# MainCircuit.net
KiCad netlist of a schematic drawn in EAGLE
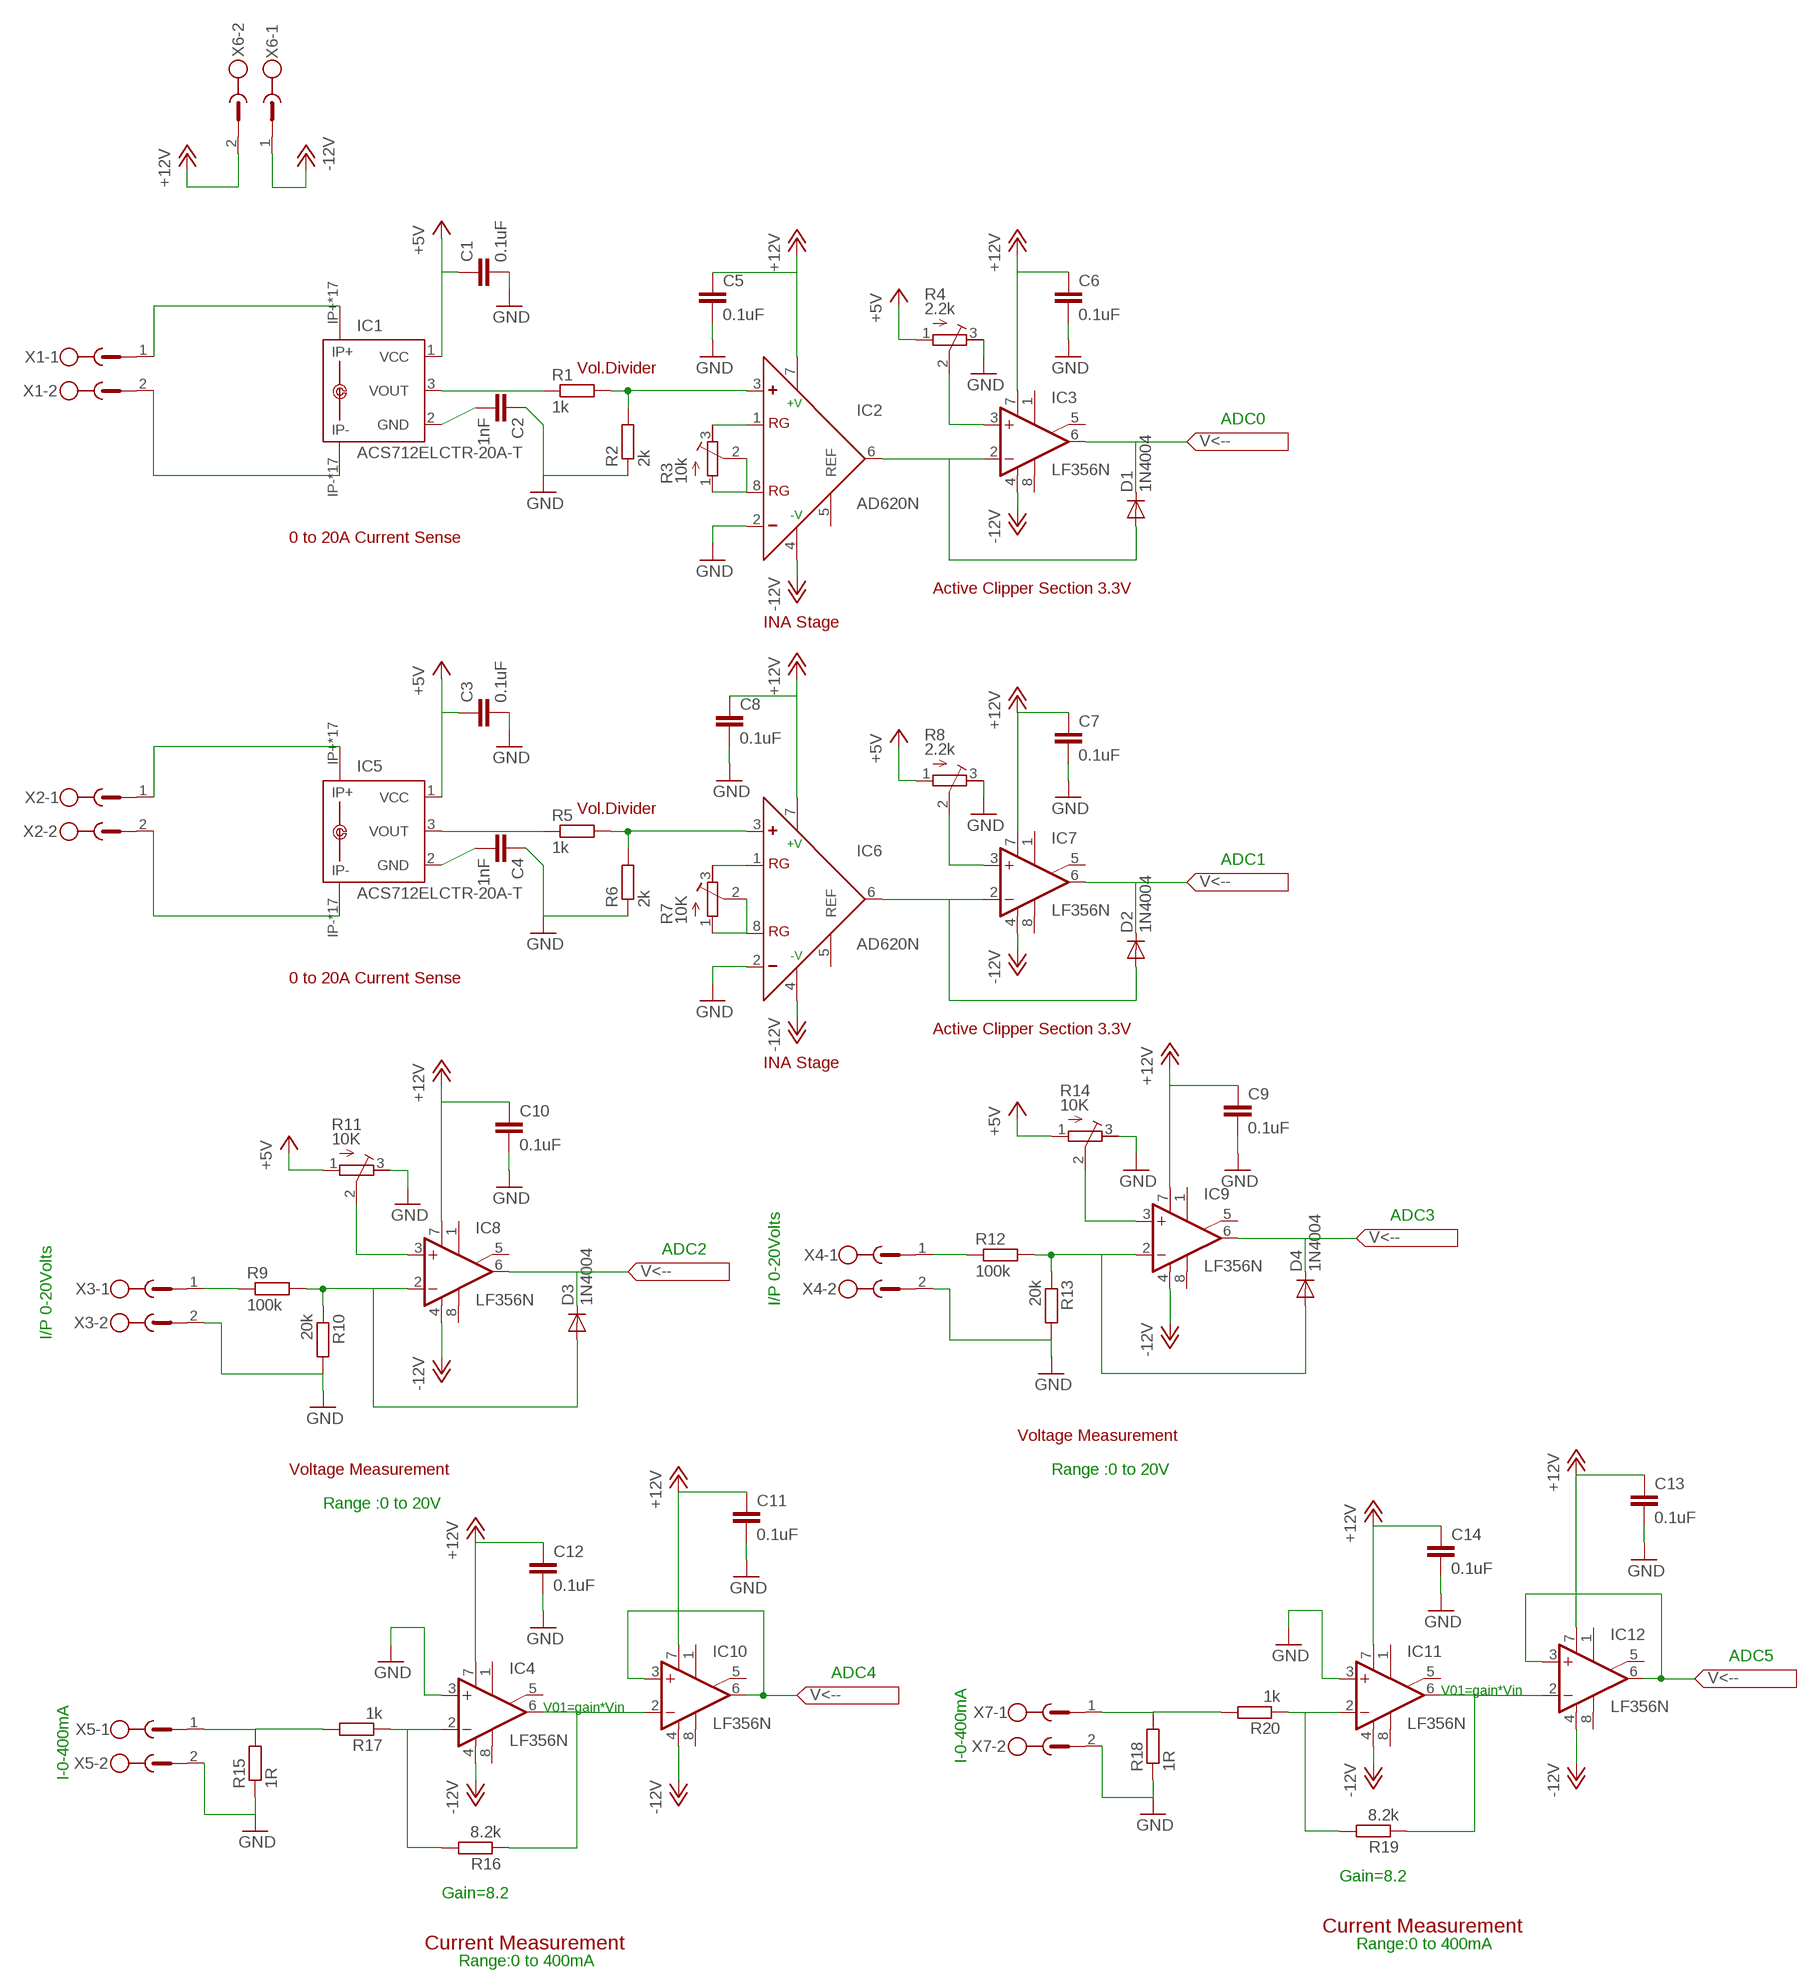
[diagram p0: schematic, sheet 1]

(export (version "E")
  (design (tool "Eeschema 10.0.6"))
  (components
    (comp (ref "C1")
      (value "0.1uF")
      (footprint "eagle-import:C025-024X044")
      (libsource (lib "eagle-import") (part "C-EU025-024X044"))
    )
    (comp (ref "C2")
      (value "1nF")
      (footprint "eagle-import:C025-024X044")
      (libsource (lib "eagle-import") (part "C-EU025-024X044"))
    )
    (comp (ref "C3")
      (value "0.1uF")
      (footprint "eagle-import:C025-024X044")
      (libsource (lib "eagle-import") (part "C-EU025-024X044"))
    )
    (comp (ref "C4")
      (value "1nF")
      (footprint "eagle-import:C025-024X044")
      (libsource (lib "eagle-import") (part "C-EU025-024X044"))
    )
    (comp (ref "C5")
      (value "0.1uF")
      (footprint "eagle-import:C025-024X044")
      (libsource (lib "eagle-import") (part "C-EU025-024X044"))
    )
    (comp (ref "C6")
      (value "0.1uF")
      (footprint "eagle-import:C025-024X044")
      (libsource (lib "eagle-import") (part "C-EU025-024X044"))
    )
    (comp (ref "C7")
      (value "0.1uF")
      (footprint "eagle-import:C025-024X044")
      (libsource (lib "eagle-import") (part "C-EU025-024X044"))
    )
    (comp (ref "C8")
      (value "0.1uF")
      (footprint "eagle-import:C025-024X044")
      (libsource (lib "eagle-import") (part "C-EU025-024X044"))
    )
    (comp (ref "C9")
      (value "0.1uF")
      (footprint "eagle-import:C025-024X044")
      (libsource (lib "eagle-import") (part "C-EU025-024X044"))
    )
    (comp (ref "C10")
      (value "0.1uF")
      (footprint "eagle-import:C025-024X044")
      (libsource (lib "eagle-import") (part "C-EU025-024X044"))
    )
    (comp (ref "C11")
      (value "0.1uF")
      (footprint "eagle-import:C025-024X044")
      (libsource (lib "eagle-import") (part "C-EU025-024X044"))
    )
    (comp (ref "C12")
      (value "0.1uF")
      (footprint "eagle-import:C025-024X044")
      (libsource (lib "eagle-import") (part "C-EU025-024X044"))
    )
    (comp (ref "C13")
      (value "0.1uF")
      (footprint "eagle-import:C025-024X044")
      (libsource (lib "eagle-import") (part "C-EU025-024X044"))
    )
    (comp (ref "C14")
      (value "0.1uF")
      (footprint "eagle-import:C025-024X044")
      (libsource (lib "eagle-import") (part "C-EU025-024X044"))
    )
    (comp (ref "D1")
      (value "1N4004")
      (footprint "eagle-import:DO41-10")
      (libsource (lib "eagle-import") (part "1N4004"))
    )
    (comp (ref "D2")
      (value "1N4004")
      (footprint "eagle-import:DO41-10")
      (libsource (lib "eagle-import") (part "1N4004"))
    )
    (comp (ref "D3")
      (value "1N4004")
      (footprint "eagle-import:DO41-10")
      (libsource (lib "eagle-import") (part "1N4004"))
    )
    (comp (ref "D4")
      (value "1N4004")
      (footprint "eagle-import:DO41-10")
      (libsource (lib "eagle-import") (part "1N4004"))
    )
    (comp (ref "IC1")
      (value "ACS712ELCTR-20A-T")
      (footprint "eagle-import:CB-PFF")
      (fields (field (name "MPN") "ACS758ECB-200B-PFF-T"))
      (libsource (lib "eagle-import") (part "ACS758ECB-200B-PFF-T"))
    )
    (comp (ref "IC2")
      (value "AD620N")
      (footprint "eagle-import:DIL08")
      (fields (field (name "MF") "ALTERA CORPORATION") (field (name "MPN") "AD620AN"))
      (libsource (lib "eagle-import") (part "AD620N"))
    )
    (comp (ref "IC3")
      (value "LF356N")
      (footprint "eagle-import:DIL08")
      (libsource (lib "eagle-import") (part "LF356N"))
    )
    (comp (ref "IC4")
      (value "LF356N")
      (footprint "eagle-import:DIL08")
      (libsource (lib "eagle-import") (part "LF356N"))
    )
    (comp (ref "IC5")
      (value "ACS712ELCTR-20A-T")
      (footprint "eagle-import:CB-PFF")
      (fields (field (name "MPN") "ACS758ECB-200B-PFF-T"))
      (libsource (lib "eagle-import") (part "ACS758ECB-200B-PFF-T"))
    )
    (comp (ref "IC6")
      (value "AD620N")
      (footprint "eagle-import:DIL08")
      (fields (field (name "MF") "ALTERA CORPORATION") (field (name "MPN") "AD620AN"))
      (libsource (lib "eagle-import") (part "AD620N"))
    )
    (comp (ref "IC7")
      (value "LF356N")
      (footprint "eagle-import:DIL08")
      (libsource (lib "eagle-import") (part "LF356N"))
    )
    (comp (ref "IC8")
      (value "LF356N")
      (footprint "eagle-import:DIL08")
      (libsource (lib "eagle-import") (part "LF356N"))
    )
    (comp (ref "IC9")
      (value "LF356N")
      (footprint "eagle-import:DIL08")
      (libsource (lib "eagle-import") (part "LF356N"))
    )
    (comp (ref "IC10")
      (value "LF356N")
      (footprint "eagle-import:DIL08")
      (libsource (lib "eagle-import") (part "LF356N"))
    )
    (comp (ref "IC11")
      (value "LF356N")
      (footprint "eagle-import:DIL08")
      (libsource (lib "eagle-import") (part "LF356N"))
    )
    (comp (ref "IC12")
      (value "LF356N")
      (footprint "eagle-import:DIL08")
      (libsource (lib "eagle-import") (part "LF356N"))
    )
    (comp (ref "R1")
      (value "1k")
      (footprint "eagle-import:0204_7")
      (libsource (lib "eagle-import") (part "R-EU_0204/7"))
    )
    (comp (ref "R2")
      (value "2k")
      (footprint "eagle-import:0204_7")
      (libsource (lib "eagle-import") (part "R-EU_0204/7"))
    )
    (comp (ref "R3")
      (value "10k")
      (footprint "eagle-import:RTRIM64W")
      (libsource (lib "eagle-import") (part "R-TRIMM64W"))
    )
    (comp (ref "R4")
      (value "2.2k")
      (footprint "eagle-import:RTRIM64W")
      (libsource (lib "eagle-import") (part "R-TRIMM64W"))
    )
    (comp (ref "R5")
      (value "1k")
      (footprint "eagle-import:0204_7")
      (libsource (lib "eagle-import") (part "R-EU_0204/7"))
    )
    (comp (ref "R6")
      (value "2k")
      (footprint "eagle-import:0204_7")
      (libsource (lib "eagle-import") (part "R-EU_0204/7"))
    )
    (comp (ref "R7")
      (value "10K")
      (footprint "eagle-import:RTRIM64W")
      (libsource (lib "eagle-import") (part "R-TRIMM64W"))
    )
    (comp (ref "R8")
      (value "2.2k")
      (footprint "eagle-import:RTRIM64W")
      (libsource (lib "eagle-import") (part "R-TRIMM64W"))
    )
    (comp (ref "R9")
      (value "100k")
      (footprint "eagle-import:0207_5V")
      (libsource (lib "eagle-import") (part "R-EU_0207/5V"))
    )
    (comp (ref "R10")
      (value "20k")
      (footprint "eagle-import:0207_5V")
      (libsource (lib "eagle-import") (part "R-EU_0207/5V"))
    )
    (comp (ref "R11")
      (value "10K")
      (footprint "eagle-import:RTRIM64W")
      (libsource (lib "eagle-import") (part "R-TRIMM64W"))
    )
    (comp (ref "R12")
      (value "100k")
      (footprint "eagle-import:0207_5V")
      (libsource (lib "eagle-import") (part "R-EU_0207/5V"))
    )
    (comp (ref "R13")
      (value "20k")
      (footprint "eagle-import:0207_5V")
      (libsource (lib "eagle-import") (part "R-EU_0207/5V"))
    )
    (comp (ref "R14")
      (value "10K")
      (footprint "eagle-import:RTRIM64W")
      (libsource (lib "eagle-import") (part "R-TRIMM64W"))
    )
    (comp (ref "R15")
      (value "1R")
      (footprint "eagle-import:0204_7")
      (libsource (lib "eagle-import") (part "R-EU_0204/7"))
    )
    (comp (ref "R16")
      (value "8.2k")
      (footprint "eagle-import:0204_7")
      (libsource (lib "eagle-import") (part "R-EU_0204/7"))
    )
    (comp (ref "R17")
      (value "1k")
      (footprint "eagle-import:0204_7")
      (libsource (lib "eagle-import") (part "R-EU_0204/7"))
    )
    (comp (ref "R18")
      (value "1R")
      (footprint "eagle-import:0204_7")
      (libsource (lib "eagle-import") (part "R-EU_0204/7"))
    )
    (comp (ref "R19")
      (value "8.2k")
      (footprint "eagle-import:0204_7")
      (libsource (lib "eagle-import") (part "R-EU_0204/7"))
    )
    (comp (ref "R20")
      (value "1k")
      (footprint "eagle-import:0204_7")
      (libsource (lib "eagle-import") (part "R-EU_0204/7"))
    )
    (comp (ref "X1")
      (value "MSTBV2")
      (footprint "eagle-import:MSTBV2")
      (libsource (lib "eagle-import") (part "MSTBV2"))
    )
    (comp (ref "X2")
      (value "MSTBV2")
      (footprint "eagle-import:MSTBV2")
      (libsource (lib "eagle-import") (part "MSTBV2"))
    )
    (comp (ref "X3")
      (value "MSTBV2")
      (footprint "eagle-import:MSTBV2")
      (libsource (lib "eagle-import") (part "MSTBV2"))
    )
    (comp (ref "X4")
      (value "MSTBV2")
      (footprint "eagle-import:MSTBV2")
      (libsource (lib "eagle-import") (part "MSTBV2"))
    )
    (comp (ref "X5")
      (value "MSTBV2")
      (footprint "eagle-import:MSTBV2")
      (libsource (lib "eagle-import") (part "MSTBV2"))
    )
    (comp (ref "X6")
      (value "MSTBV2")
      (footprint "eagle-import:MSTBV2")
      (libsource (lib "eagle-import") (part "MSTBV2"))
    )
    (comp (ref "X7")
      (value "MSTBV2")
      (footprint "eagle-import:MSTBV2")
      (libsource (lib "eagle-import") (part "MSTBV2"))
    )
  )
  (nets
    (net (code "1") (name "+5V") (class "Default")
      (node (ref "C1") (pin "1") (pinfunction "1_1") (pintype "passive"))
      (node (ref "C3") (pin "1") (pinfunction "1_1") (pintype "passive"))
      (node (ref "IC1") (pin "1") (pinfunction "VCC_1") (pintype "power_in"))
      (node (ref "IC5") (pin "1") (pinfunction "VCC_1") (pintype "power_in"))
      (node (ref "R11") (pin "1") (pinfunction "A_1") (pintype "passive"))
      (node (ref "R14") (pin "1") (pinfunction "A_1") (pintype "passive"))
      (node (ref "R4") (pin "1") (pinfunction "A_1") (pintype "passive"))
      (node (ref "R8") (pin "1") (pinfunction "A_1") (pintype "passive"))
    )
    (net (code "2") (name "+12V") (class "Default")
      (node (ref "C10") (pin "1") (pinfunction "1_1") (pintype "passive"))
      (node (ref "C11") (pin "1") (pinfunction "1_1") (pintype "passive"))
      (node (ref "C12") (pin "1") (pinfunction "1_1") (pintype "passive"))
      (node (ref "C13") (pin "1") (pinfunction "1_1") (pintype "passive"))
      (node (ref "C14") (pin "1") (pinfunction "1_1") (pintype "passive"))
      (node (ref "C5") (pin "1") (pinfunction "1_1") (pintype "passive"))
      (node (ref "C6") (pin "1") (pinfunction "1_1") (pintype "passive"))
      (node (ref "C7") (pin "1") (pinfunction "1_1") (pintype "passive"))
      (node (ref "C8") (pin "1") (pinfunction "1_1") (pintype "passive"))
      (node (ref "C9") (pin "1") (pinfunction "1_1") (pintype "passive"))
      (node (ref "IC10") (pin "7") (pinfunction "V+_7") (pintype "power_in"))
      (node (ref "IC11") (pin "7") (pinfunction "V+_7") (pintype "power_in"))
      (node (ref "IC12") (pin "7") (pinfunction "V+_7") (pintype "power_in"))
      (node (ref "IC2") (pin "7") (pinfunction "+V_7") (pintype "power_in"))
      (node (ref "IC3") (pin "7") (pinfunction "V+_7") (pintype "power_in"))
      (node (ref "IC4") (pin "7") (pinfunction "V+_7") (pintype "power_in"))
      (node (ref "IC6") (pin "7") (pinfunction "+V_7") (pintype "power_in"))
      (node (ref "IC7") (pin "7") (pinfunction "V+_7") (pintype "power_in"))
      (node (ref "IC8") (pin "7") (pinfunction "V+_7") (pintype "power_in"))
      (node (ref "IC9") (pin "7") (pinfunction "V+_7") (pintype "power_in"))
      (node (ref "X6") (pin "2") (pinfunction "SK_2") (pintype "passive"))
    )
    (net (code "3") (name "-12V") (class "Default")
      (node (ref "IC10") (pin "4") (pinfunction "V-_4") (pintype "power_in"))
      (node (ref "IC11") (pin "4") (pinfunction "V-_4") (pintype "power_in"))
      (node (ref "IC12") (pin "4") (pinfunction "V-_4") (pintype "power_in"))
      (node (ref "IC2") (pin "4") (pinfunction "-V_4") (pintype "power_in"))
      (node (ref "IC3") (pin "4") (pinfunction "V-_4") (pintype "power_in"))
      (node (ref "IC4") (pin "4") (pinfunction "V-_4") (pintype "power_in"))
      (node (ref "IC6") (pin "4") (pinfunction "-V_4") (pintype "power_in"))
      (node (ref "IC7") (pin "4") (pinfunction "V-_4") (pintype "power_in"))
      (node (ref "IC8") (pin "4") (pinfunction "V-_4") (pintype "power_in"))
      (node (ref "IC9") (pin "4") (pinfunction "V-_4") (pintype "power_in"))
      (node (ref "X6") (pin "1") (pinfunction "SK_1") (pintype "passive"))
    )
    (net (code "4") (name "GND") (class "Default")
      (node (ref "C1") (pin "2") (pinfunction "2_2") (pintype "passive"))
      (node (ref "C10") (pin "2") (pinfunction "2_2") (pintype "passive"))
      (node (ref "C11") (pin "2") (pinfunction "2_2") (pintype "passive"))
      (node (ref "C12") (pin "2") (pinfunction "2_2") (pintype "passive"))
      (node (ref "C13") (pin "2") (pinfunction "2_2") (pintype "passive"))
      (node (ref "C14") (pin "2") (pinfunction "2_2") (pintype "passive"))
      (node (ref "C2") (pin "1") (pinfunction "1_1") (pintype "passive"))
      (node (ref "C3") (pin "2") (pinfunction "2_2") (pintype "passive"))
      (node (ref "C4") (pin "1") (pinfunction "1_1") (pintype "passive"))
      (node (ref "C5") (pin "2") (pinfunction "2_2") (pintype "passive"))
      (node (ref "C6") (pin "2") (pinfunction "2_2") (pintype "passive"))
      (node (ref "C7") (pin "2") (pinfunction "2_2") (pintype "passive"))
      (node (ref "C8") (pin "2") (pinfunction "2_2") (pintype "passive"))
      (node (ref "C9") (pin "2") (pinfunction "2_2") (pintype "passive"))
      (node (ref "IC11") (pin "3") (pinfunction "+IN_3") (pintype "input"))
      (node (ref "IC2") (pin "2") (pinfunction "-_2") (pintype "input"))
      (node (ref "IC4") (pin "3") (pinfunction "+IN_3") (pintype "input"))
      (node (ref "IC6") (pin "2") (pinfunction "-_2") (pintype "input"))
      (node (ref "R10") (pin "2") (pinfunction "2_2") (pintype "passive"))
      (node (ref "R11") (pin "3") (pinfunction "E_3") (pintype "passive"))
      (node (ref "R13") (pin "2") (pinfunction "2_2") (pintype "passive"))
      (node (ref "R14") (pin "3") (pinfunction "E_3") (pintype "passive"))
      (node (ref "R15") (pin "1") (pinfunction "1_1") (pintype "passive"))
      (node (ref "R18") (pin "1") (pinfunction "1_1") (pintype "passive"))
      (node (ref "R2") (pin "1") (pinfunction "1_1") (pintype "passive"))
      (node (ref "R4") (pin "3") (pinfunction "E_3") (pintype "passive"))
      (node (ref "R6") (pin "1") (pinfunction "1_1") (pintype "passive"))
      (node (ref "R8") (pin "3") (pinfunction "E_3") (pintype "passive"))
      (node (ref "X3") (pin "2") (pinfunction "SK_2") (pintype "passive"))
      (node (ref "X4") (pin "2") (pinfunction "SK_2") (pintype "passive"))
      (node (ref "X5") (pin "2") (pinfunction "SK_2") (pintype "passive"))
      (node (ref "X7") (pin "2") (pinfunction "SK_2") (pintype "passive"))
    )
    (net (code "5") (name "Net-(IC1-GND)") (class "Default")
      (node (ref "C2") (pin "2") (pinfunction "2_2") (pintype "passive"))
      (node (ref "IC1") (pin "2") (pinfunction "GND_2") (pintype "power_in"))
    )
    (net (code "6") (name "Net-(IC1-VOUT)") (class "Default")
      (node (ref "IC1") (pin "3") (pinfunction "VOUT_3") (pintype "output"))
      (node (ref "R1") (pin "1") (pinfunction "1_1") (pintype "passive"))
    )
    (net (code "7") (name "Net-(IC2-+)") (class "Default")
      (node (ref "IC2") (pin "3") (pinfunction "+_3") (pintype "input"))
      (node (ref "R1") (pin "2") (pinfunction "2_2") (pintype "passive"))
      (node (ref "R2") (pin "2") (pinfunction "2_2") (pintype "passive"))
    )
    (net (code "8") (name "Net-(IC2-OUT)") (class "Default")
      (node (ref "D1") (pin "A") (pinfunction "A_A") (pintype "passive"))
      (node (ref "IC2") (pin "6") (pinfunction "OUT_6") (pintype "output"))
      (node (ref "IC3") (pin "2") (pinfunction "-IN_2") (pintype "input"))
    )
    (net (code "9") (name "Net-(IC3-+IN)") (class "Default")
      (node (ref "IC3") (pin "3") (pinfunction "+IN_3") (pintype "input"))
      (node (ref "R4") (pin "2") (pinfunction "S_2") (pintype "passive"))
    )
    (net (code "10") (name "Net-(IC3-OUT)") (class "Default")
      (node (ref "D1") (pin "C") (pinfunction "C_C") (pintype "passive"))
      (node (ref "IC3") (pin "6") (pinfunction "OUT_6") (pintype "output"))
    )
    (net (code "11") (name "Net-(IC4--IN)") (class "Default")
      (node (ref "IC4") (pin "2") (pinfunction "-IN_2") (pintype "input"))
      (node (ref "R16") (pin "2") (pinfunction "2_2") (pintype "passive"))
      (node (ref "R17") (pin "1") (pinfunction "1_1") (pintype "passive"))
    )
    (net (code "12") (name "Net-(IC5-GND)") (class "Default")
      (node (ref "C4") (pin "2") (pinfunction "2_2") (pintype "passive"))
      (node (ref "IC5") (pin "2") (pinfunction "GND_2") (pintype "power_in"))
    )
    (net (code "13") (name "Net-(IC5-VOUT)") (class "Default")
      (node (ref "IC5") (pin "3") (pinfunction "VOUT_3") (pintype "output"))
      (node (ref "R5") (pin "1") (pinfunction "1_1") (pintype "passive"))
    )
    (net (code "14") (name "Net-(IC6-+)") (class "Default")
      (node (ref "IC6") (pin "3") (pinfunction "+_3") (pintype "input"))
      (node (ref "R5") (pin "2") (pinfunction "2_2") (pintype "passive"))
      (node (ref "R6") (pin "2") (pinfunction "2_2") (pintype "passive"))
    )
    (net (code "15") (name "Net-(IC6-OUT)") (class "Default")
      (node (ref "D2") (pin "A") (pinfunction "A_A") (pintype "passive"))
      (node (ref "IC6") (pin "6") (pinfunction "OUT_6") (pintype "output"))
      (node (ref "IC7") (pin "2") (pinfunction "-IN_2") (pintype "input"))
    )
    (net (code "16") (name "Net-(IC7-+IN)") (class "Default")
      (node (ref "IC7") (pin "3") (pinfunction "+IN_3") (pintype "input"))
      (node (ref "R8") (pin "2") (pinfunction "S_2") (pintype "passive"))
    )
    (net (code "17") (name "Net-(IC7-OUT)") (class "Default")
      (node (ref "D2") (pin "C") (pinfunction "C_C") (pintype "passive"))
      (node (ref "IC7") (pin "6") (pinfunction "OUT_6") (pintype "output"))
    )
    (net (code "18") (name "Net-(IC8-+IN)") (class "Default")
      (node (ref "IC8") (pin "3") (pinfunction "+IN_3") (pintype "input"))
      (node (ref "R11") (pin "2") (pinfunction "S_2") (pintype "passive"))
    )
    (net (code "19") (name "Net-(IC8--IN)") (class "Default")
      (node (ref "D3") (pin "A") (pinfunction "A_A") (pintype "passive"))
      (node (ref "IC8") (pin "2") (pinfunction "-IN_2") (pintype "input"))
      (node (ref "R10") (pin "1") (pinfunction "1_1") (pintype "passive"))
      (node (ref "R9") (pin "2") (pinfunction "2_2") (pintype "passive"))
    )
    (net (code "20") (name "Net-(IC8-OUT)") (class "Default")
      (node (ref "D3") (pin "C") (pinfunction "C_C") (pintype "passive"))
      (node (ref "IC8") (pin "6") (pinfunction "OUT_6") (pintype "output"))
    )
    (net (code "21") (name "Net-(IC9-+IN)") (class "Default")
      (node (ref "IC9") (pin "3") (pinfunction "+IN_3") (pintype "input"))
      (node (ref "R14") (pin "2") (pinfunction "S_2") (pintype "passive"))
    )
    (net (code "22") (name "Net-(IC9--IN)") (class "Default")
      (node (ref "D4") (pin "A") (pinfunction "A_A") (pintype "passive"))
      (node (ref "IC9") (pin "2") (pinfunction "-IN_2") (pintype "input"))
      (node (ref "R12") (pin "2") (pinfunction "2_2") (pintype "passive"))
      (node (ref "R13") (pin "1") (pinfunction "1_1") (pintype "passive"))
    )
    (net (code "23") (name "Net-(IC9-OUT)") (class "Default")
      (node (ref "D4") (pin "C") (pinfunction "C_C") (pintype "passive"))
      (node (ref "IC9") (pin "6") (pinfunction "OUT_6") (pintype "output"))
    )
    (net (code "24") (name "Net-(IC10-+IN)") (class "Default")
      (node (ref "IC10") (pin "3") (pinfunction "+IN_3") (pintype "input"))
      (node (ref "IC10") (pin "6") (pinfunction "OUT_6") (pintype "output"))
    )
    (net (code "25") (name "Net-(IC10--IN)") (class "Default")
      (node (ref "IC10") (pin "2") (pinfunction "-IN_2") (pintype "input"))
      (node (ref "IC4") (pin "6") (pinfunction "OUT_6") (pintype "output"))
      (node (ref "R16") (pin "1") (pinfunction "1_1") (pintype "passive"))
    )
    (net (code "26") (name "Net-(IC11--IN)") (class "Default")
      (node (ref "IC11") (pin "2") (pinfunction "-IN_2") (pintype "input"))
      (node (ref "R19") (pin "2") (pinfunction "2_2") (pintype "passive"))
      (node (ref "R20") (pin "1") (pinfunction "1_1") (pintype "passive"))
    )
    (net (code "27") (name "Net-(IC11-OUT)") (class "Default")
      (node (ref "IC11") (pin "6") (pinfunction "OUT_6") (pintype "output"))
      (node (ref "IC12") (pin "2") (pinfunction "-IN_2") (pintype "input"))
      (node (ref "R19") (pin "1") (pinfunction "1_1") (pintype "passive"))
    )
    (net (code "28") (name "Net-(IC12-+IN)") (class "Default")
      (node (ref "IC12") (pin "3") (pinfunction "+IN_3") (pintype "input"))
      (node (ref "IC12") (pin "6") (pinfunction "OUT_6") (pintype "output"))
    )
    (net (code "29") (name "Net-(R3-A)") (class "Default")
      (node (ref "IC2") (pin "8") (pinfunction "RG_8") (pintype "passive"))
      (node (ref "R3") (pin "1") (pinfunction "A_1") (pintype "passive"))
      (node (ref "R3") (pin "2") (pinfunction "S_2") (pintype "passive"))
    )
    (net (code "30") (name "Net-(R3-E)") (class "Default")
      (node (ref "IC2") (pin "1") (pinfunction "RG_1") (pintype "passive"))
      (node (ref "R3") (pin "3") (pinfunction "E_3") (pintype "passive"))
    )
    (net (code "31") (name "Net-(R7-A)") (class "Default")
      (node (ref "IC6") (pin "8") (pinfunction "RG_8") (pintype "passive"))
      (node (ref "R7") (pin "1") (pinfunction "A_1") (pintype "passive"))
      (node (ref "R7") (pin "2") (pinfunction "S_2") (pintype "passive"))
    )
    (net (code "32") (name "Net-(R7-E)") (class "Default")
      (node (ref "IC6") (pin "1") (pinfunction "RG_1") (pintype "passive"))
      (node (ref "R7") (pin "3") (pinfunction "E_3") (pintype "passive"))
    )
    (net (code "33") (name "Net-(X1A-SK)") (class "Default")
      (node (ref "IC1") (pin "IP+") (pinfunction "IP+_IP+") (pintype "passive"))
      (node (ref "IC1") (pin "IP+@10") (pinfunction "IP+_IP+@10") (pintype "passive"))
      (node (ref "IC1") (pin "IP+@11") (pinfunction "IP+_IP+@11") (pintype "passive"))
      (node (ref "IC1") (pin "IP+@12") (pinfunction "IP+_IP+@12") (pintype "passive"))
      (node (ref "IC1") (pin "IP+@13") (pinfunction "IP+_IP+@13") (pintype "passive"))
      (node (ref "IC1") (pin "IP+@14") (pinfunction "IP+_IP+@14") (pintype "passive"))
      (node (ref "IC1") (pin "IP+@15") (pinfunction "IP+_IP+@15") (pintype "passive"))
      (node (ref "IC1") (pin "IP+@16") (pinfunction "IP+_IP+@16") (pintype "passive"))
      (node (ref "IC1") (pin "IP+@17") (pinfunction "IP+_IP+@17") (pintype "passive"))
      (node (ref "IC1") (pin "IP+@2") (pinfunction "IP+_IP+@2") (pintype "passive"))
      (node (ref "IC1") (pin "IP+@3") (pinfunction "IP+_IP+@3") (pintype "passive"))
      (node (ref "IC1") (pin "IP+@4") (pinfunction "IP+_IP+@4") (pintype "passive"))
      (node (ref "IC1") (pin "IP+@5") (pinfunction "IP+_IP+@5") (pintype "passive"))
      (node (ref "IC1") (pin "IP+@6") (pinfunction "IP+_IP+@6") (pintype "passive"))
      (node (ref "IC1") (pin "IP+@7") (pinfunction "IP+_IP+@7") (pintype "passive"))
      (node (ref "IC1") (pin "IP+@8") (pinfunction "IP+_IP+@8") (pintype "passive"))
      (node (ref "IC1") (pin "IP+@9") (pinfunction "IP+_IP+@9") (pintype "passive"))
      (node (ref "X1") (pin "1") (pinfunction "SK_1") (pintype "passive"))
    )
    (net (code "34") (name "Net-(X1B-SK)") (class "Default")
      (node (ref "IC1") (pin "IP-") (pinfunction "IP-_IP-") (pintype "passive"))
      (node (ref "IC1") (pin "IP-@10") (pinfunction "IP-_IP-@10") (pintype "passive"))
      (node (ref "IC1") (pin "IP-@11") (pinfunction "IP-_IP-@11") (pintype "passive"))
      (node (ref "IC1") (pin "IP-@12") (pinfunction "IP-_IP-@12") (pintype "passive"))
      (node (ref "IC1") (pin "IP-@13") (pinfunction "IP-_IP-@13") (pintype "passive"))
      (node (ref "IC1") (pin "IP-@14") (pinfunction "IP-_IP-@14") (pintype "passive"))
      (node (ref "IC1") (pin "IP-@15") (pinfunction "IP-_IP-@15") (pintype "passive"))
      (node (ref "IC1") (pin "IP-@16") (pinfunction "IP-_IP-@16") (pintype "passive"))
      (node (ref "IC1") (pin "IP-@17") (pinfunction "IP-_IP-@17") (pintype "passive"))
      (node (ref "IC1") (pin "IP-@2") (pinfunction "IP-_IP-@2") (pintype "passive"))
      (node (ref "IC1") (pin "IP-@3") (pinfunction "IP-_IP-@3") (pintype "passive"))
      (node (ref "IC1") (pin "IP-@4") (pinfunction "IP-_IP-@4") (pintype "passive"))
      (node (ref "IC1") (pin "IP-@5") (pinfunction "IP-_IP-@5") (pintype "passive"))
      (node (ref "IC1") (pin "IP-@6") (pinfunction "IP-_IP-@6") (pintype "passive"))
      (node (ref "IC1") (pin "IP-@7") (pinfunction "IP-_IP-@7") (pintype "passive"))
      (node (ref "IC1") (pin "IP-@8") (pinfunction "IP-_IP-@8") (pintype "passive"))
      (node (ref "IC1") (pin "IP-@9") (pinfunction "IP-_IP-@9") (pintype "passive"))
      (node (ref "X1") (pin "2") (pinfunction "SK_2") (pintype "passive"))
    )
    (net (code "35") (name "Net-(X2A-SK)") (class "Default")
      (node (ref "IC5") (pin "IP+") (pinfunction "IP+_IP+") (pintype "passive"))
      (node (ref "IC5") (pin "IP+@10") (pinfunction "IP+_IP+@10") (pintype "passive"))
      (node (ref "IC5") (pin "IP+@11") (pinfunction "IP+_IP+@11") (pintype "passive"))
      (node (ref "IC5") (pin "IP+@12") (pinfunction "IP+_IP+@12") (pintype "passive"))
      (node (ref "IC5") (pin "IP+@13") (pinfunction "IP+_IP+@13") (pintype "passive"))
      (node (ref "IC5") (pin "IP+@14") (pinfunction "IP+_IP+@14") (pintype "passive"))
      (node (ref "IC5") (pin "IP+@15") (pinfunction "IP+_IP+@15") (pintype "passive"))
      (node (ref "IC5") (pin "IP+@16") (pinfunction "IP+_IP+@16") (pintype "passive"))
      (node (ref "IC5") (pin "IP+@17") (pinfunction "IP+_IP+@17") (pintype "passive"))
      (node (ref "IC5") (pin "IP+@2") (pinfunction "IP+_IP+@2") (pintype "passive"))
      (node (ref "IC5") (pin "IP+@3") (pinfunction "IP+_IP+@3") (pintype "passive"))
      (node (ref "IC5") (pin "IP+@4") (pinfunction "IP+_IP+@4") (pintype "passive"))
      (node (ref "IC5") (pin "IP+@5") (pinfunction "IP+_IP+@5") (pintype "passive"))
      (node (ref "IC5") (pin "IP+@6") (pinfunction "IP+_IP+@6") (pintype "passive"))
      (node (ref "IC5") (pin "IP+@7") (pinfunction "IP+_IP+@7") (pintype "passive"))
      (node (ref "IC5") (pin "IP+@8") (pinfunction "IP+_IP+@8") (pintype "passive"))
      (node (ref "IC5") (pin "IP+@9") (pinfunction "IP+_IP+@9") (pintype "passive"))
      (node (ref "X2") (pin "1") (pinfunction "SK_1") (pintype "passive"))
    )
    (net (code "36") (name "Net-(X2B-SK)") (class "Default")
      (node (ref "IC5") (pin "IP-") (pinfunction "IP-_IP-") (pintype "passive"))
      (node (ref "IC5") (pin "IP-@10") (pinfunction "IP-_IP-@10") (pintype "passive"))
      (node (ref "IC5") (pin "IP-@11") (pinfunction "IP-_IP-@11") (pintype "passive"))
      (node (ref "IC5") (pin "IP-@12") (pinfunction "IP-_IP-@12") (pintype "passive"))
      (node (ref "IC5") (pin "IP-@13") (pinfunction "IP-_IP-@13") (pintype "passive"))
      (node (ref "IC5") (pin "IP-@14") (pinfunction "IP-_IP-@14") (pintype "passive"))
      (node (ref "IC5") (pin "IP-@15") (pinfunction "IP-_IP-@15") (pintype "passive"))
      (node (ref "IC5") (pin "IP-@16") (pinfunction "IP-_IP-@16") (pintype "passive"))
      (node (ref "IC5") (pin "IP-@17") (pinfunction "IP-_IP-@17") (pintype "passive"))
      (node (ref "IC5") (pin "IP-@2") (pinfunction "IP-_IP-@2") (pintype "passive"))
      (node (ref "IC5") (pin "IP-@3") (pinfunction "IP-_IP-@3") (pintype "passive"))
      (node (ref "IC5") (pin "IP-@4") (pinfunction "IP-_IP-@4") (pintype "passive"))
      (node (ref "IC5") (pin "IP-@5") (pinfunction "IP-_IP-@5") (pintype "passive"))
      (node (ref "IC5") (pin "IP-@6") (pinfunction "IP-_IP-@6") (pintype "passive"))
      (node (ref "IC5") (pin "IP-@7") (pinfunction "IP-_IP-@7") (pintype "passive"))
      (node (ref "IC5") (pin "IP-@8") (pinfunction "IP-_IP-@8") (pintype "passive"))
      (node (ref "IC5") (pin "IP-@9") (pinfunction "IP-_IP-@9") (pintype "passive"))
      (node (ref "X2") (pin "2") (pinfunction "SK_2") (pintype "passive"))
    )
    (net (code "37") (name "Net-(X3A-SK)") (class "Default")
      (node (ref "R9") (pin "1") (pinfunction "1_1") (pintype "passive"))
      (node (ref "X3") (pin "1") (pinfunction "SK_1") (pintype "passive"))
    )
    (net (code "38") (name "Net-(X4A-SK)") (class "Default")
      (node (ref "R12") (pin "1") (pinfunction "1_1") (pintype "passive"))
      (node (ref "X4") (pin "1") (pinfunction "SK_1") (pintype "passive"))
    )
    (net (code "39") (name "Net-(X5A-SK)") (class "Default")
      (node (ref "R15") (pin "2") (pinfunction "2_2") (pintype "passive"))
      (node (ref "R17") (pin "2") (pinfunction "2_2") (pintype "passive"))
      (node (ref "X5") (pin "1") (pinfunction "SK_1") (pintype "passive"))
    )
    (net (code "40") (name "Net-(X7A-SK)") (class "Default")
      (node (ref "R18") (pin "2") (pinfunction "2_2") (pintype "passive"))
      (node (ref "R20") (pin "2") (pinfunction "2_2") (pintype "passive"))
      (node (ref "X7") (pin "1") (pinfunction "SK_1") (pintype "passive"))
    )
    (net (code "41") (name "unconnected-(IC2-REF-Pad5)") (class "Default")
      (node (ref "IC2") (pin "5") (pinfunction "REF_5") (pintype "passive"))
    )
    (net (code "42") (name "unconnected-(IC3-ON1-Pad1)") (class "Default")
      (node (ref "IC3") (pin "1") (pinfunction "ON1_1") (pintype "passive"))
    )
    (net (code "43") (name "unconnected-(IC3-ON2-Pad5)") (class "Default")
      (node (ref "IC3") (pin "5") (pinfunction "ON2_5") (pintype "passive"))
    )
    (net (code "44") (name "unconnected-(IC3-OPT-Pad8)") (class "Default")
      (node (ref "IC3") (pin "8") (pinfunction "OPT_8") (pintype "passive"))
    )
    (net (code "45") (name "unconnected-(IC4-ON1-Pad1)") (class "Default")
      (node (ref "IC4") (pin "1") (pinfunction "ON1_1") (pintype "passive"))
    )
    (net (code "46") (name "unconnected-(IC4-ON2-Pad5)") (class "Default")
      (node (ref "IC4") (pin "5") (pinfunction "ON2_5") (pintype "passive"))
    )
    (net (code "47") (name "unconnected-(IC4-OPT-Pad8)") (class "Default")
      (node (ref "IC4") (pin "8") (pinfunction "OPT_8") (pintype "passive"))
    )
    (net (code "48") (name "unconnected-(IC6-REF-Pad5)") (class "Default")
      (node (ref "IC6") (pin "5") (pinfunction "REF_5") (pintype "passive"))
    )
    (net (code "49") (name "unconnected-(IC7-ON1-Pad1)") (class "Default")
      (node (ref "IC7") (pin "1") (pinfunction "ON1_1") (pintype "passive"))
    )
    (net (code "50") (name "unconnected-(IC7-ON2-Pad5)") (class "Default")
      (node (ref "IC7") (pin "5") (pinfunction "ON2_5") (pintype "passive"))
    )
    (net (code "51") (name "unconnected-(IC7-OPT-Pad8)") (class "Default")
      (node (ref "IC7") (pin "8") (pinfunction "OPT_8") (pintype "passive"))
    )
    (net (code "52") (name "unconnected-(IC8-ON1-Pad1)") (class "Default")
      (node (ref "IC8") (pin "1") (pinfunction "ON1_1") (pintype "passive"))
    )
    (net (code "53") (name "unconnected-(IC8-ON2-Pad5)") (class "Default")
      (node (ref "IC8") (pin "5") (pinfunction "ON2_5") (pintype "passive"))
    )
    (net (code "54") (name "unconnected-(IC8-OPT-Pad8)") (class "Default")
      (node (ref "IC8") (pin "8") (pinfunction "OPT_8") (pintype "passive"))
    )
    (net (code "55") (name "unconnected-(IC9-ON1-Pad1)") (class "Default")
      (node (ref "IC9") (pin "1") (pinfunction "ON1_1") (pintype "passive"))
    )
    (net (code "56") (name "unconnected-(IC9-ON2-Pad5)") (class "Default")
      (node (ref "IC9") (pin "5") (pinfunction "ON2_5") (pintype "passive"))
    )
    (net (code "57") (name "unconnected-(IC9-OPT-Pad8)") (class "Default")
      (node (ref "IC9") (pin "8") (pinfunction "OPT_8") (pintype "passive"))
    )
    (net (code "58") (name "unconnected-(IC10-ON1-Pad1)") (class "Default")
      (node (ref "IC10") (pin "1") (pinfunction "ON1_1") (pintype "passive"))
    )
    (net (code "59") (name "unconnected-(IC10-ON2-Pad5)") (class "Default")
      (node (ref "IC10") (pin "5") (pinfunction "ON2_5") (pintype "passive"))
    )
    (net (code "60") (name "unconnected-(IC10-OPT-Pad8)") (class "Default")
      (node (ref "IC10") (pin "8") (pinfunction "OPT_8") (pintype "passive"))
    )
    (net (code "61") (name "unconnected-(IC11-ON1-Pad1)") (class "Default")
      (node (ref "IC11") (pin "1") (pinfunction "ON1_1") (pintype "passive"))
    )
    (net (code "62") (name "unconnected-(IC11-ON2-Pad5)") (class "Default")
      (node (ref "IC11") (pin "5") (pinfunction "ON2_5") (pintype "passive"))
    )
    (net (code "63") (name "unconnected-(IC11-OPT-Pad8)") (class "Default")
      (node (ref "IC11") (pin "8") (pinfunction "OPT_8") (pintype "passive"))
    )
    (net (code "64") (name "unconnected-(IC12-ON1-Pad1)") (class "Default")
      (node (ref "IC12") (pin "1") (pinfunction "ON1_1") (pintype "passive"))
    )
    (net (code "65") (name "unconnected-(IC12-ON2-Pad5)") (class "Default")
      (node (ref "IC12") (pin "5") (pinfunction "ON2_5") (pintype "passive"))
    )
    (net (code "66") (name "unconnected-(IC12-OPT-Pad8)") (class "Default")
      (node (ref "IC12") (pin "8") (pinfunction "OPT_8") (pintype "passive"))
    )
  )
)
